# PTC_Heater_V2.net
KiCad netlist of a schematic drawn in Altium Designer
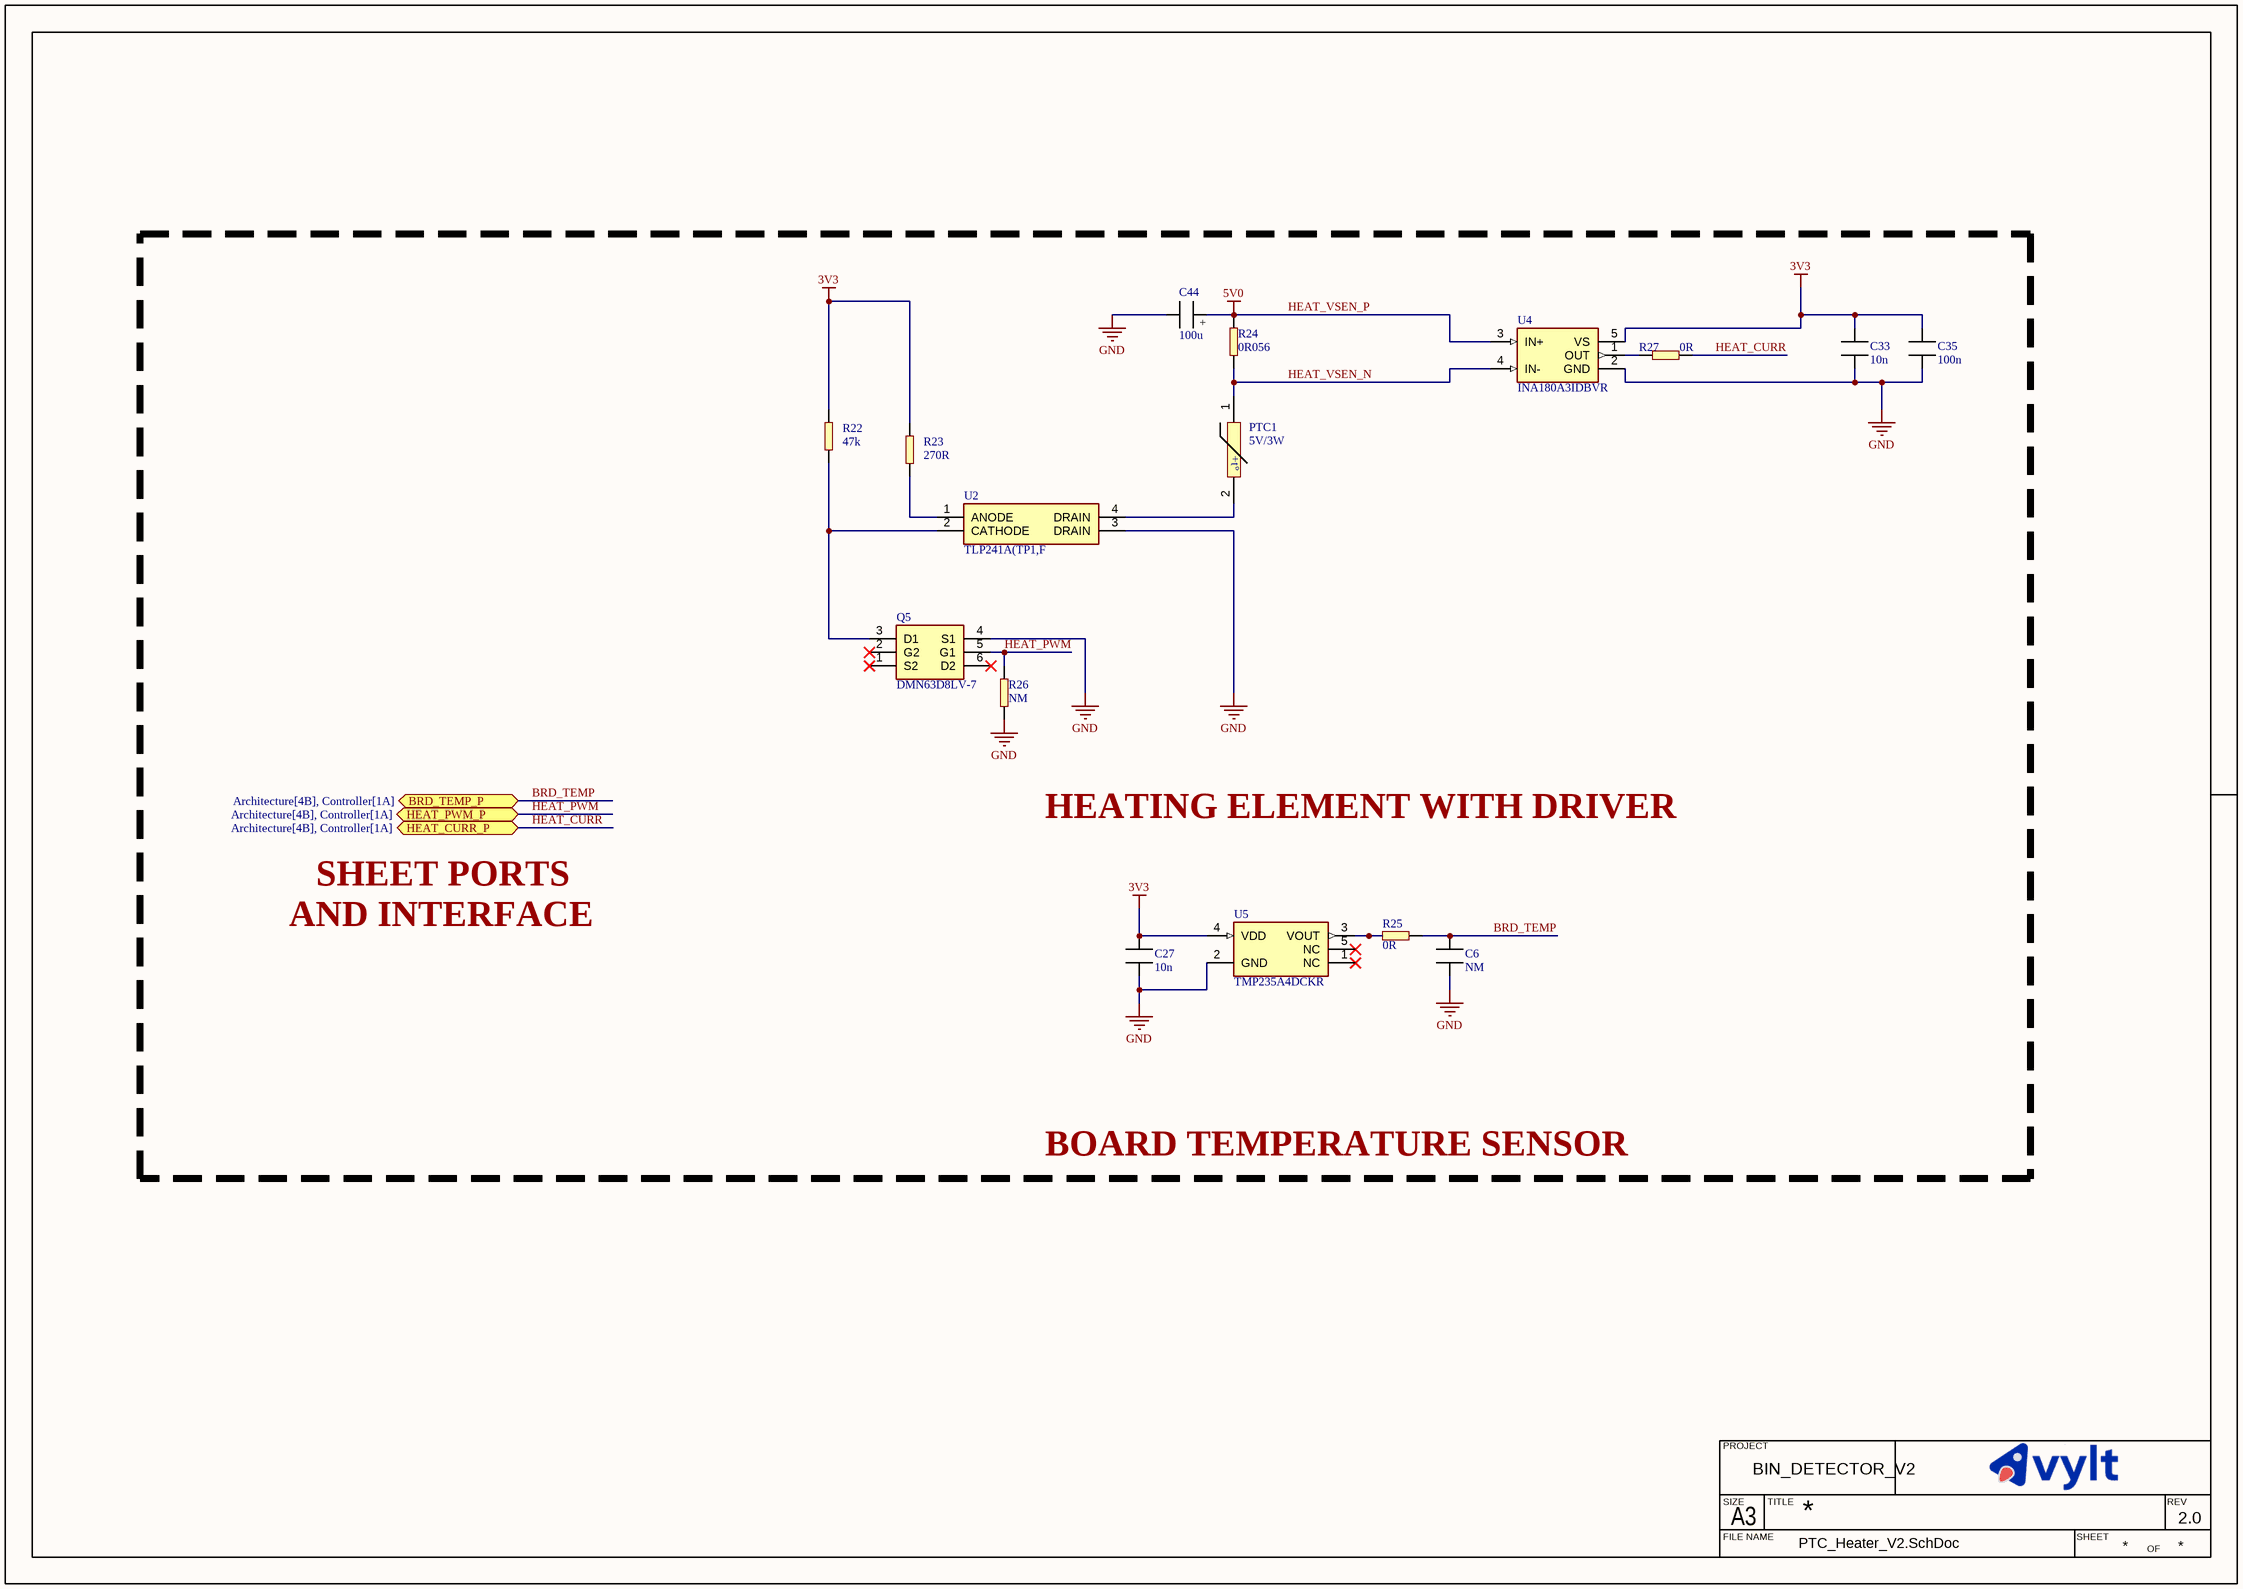
[diagram p0: PTC_Heater_V2.SchDoc]

(export (version "E")
  (design (tool "Eeschema 10.0.6"))
  (components
    (comp (ref "C6")
      (value "NM")
      (footprint "CAPC1608X10N")
      (description "Chip Capacitor, 2-Leads, Body 1.60x0.80mm, IPC Medium Density")
      (fields (field (name "Comment") "ERP_102-1"))
      (libsource (lib "Capacitor") (part "MLCC_0603"))
    )
    (comp (ref "C27")
      (value "10n")
      (footprint "CAPC1608X10N")
      (description "MLCC_0603")
      (fields (field (name "Comment") "ERP_102-1"))
      (libsource (lib "Capacitor") (part "MLCC_0603"))
    )
    (comp (ref "C33")
      (value "10n")
      (footprint "CAPC1608X10N")
      (description "Chip Capacitor, 2-Leads, Body 1.60x0.80mm, IPC Medium Density")
      (fields (field (name "Comment") "ERP_102-1"))
      (libsource (lib "Capacitor") (part "MLCC_0603"))
    )
    (comp (ref "C35")
      (value "100n")
      (footprint "CAPC1608X10N")
      (description "Chip Capacitor, 2-Leads, Body 1.60x0.80mm, IPC Medium Density")
      (fields (field (name "Comment") "ERP_102-1"))
      (libsource (lib "Capacitor") (part "MLCC_0603"))
    )
    (comp (ref "C44")
      (value "100u")
      (footprint "CAP_6.3_7.7")
      (description "Electrolytic Capacitor SMD 6.3x7.7")
      (fields (field (name "Comment") "ERP_102-2"))
      (libsource (lib "ElectrolyticCapacitor") (part "CAP_6.3_7.7"))
    )
    (comp (ref "PTC1")
      (value "5V/3W")
      (footprint "FIT0844")
      (description "PTC HEATER 5V 3W")
      (fields (field (name "Comment") "FIT0844"))
      (libsource (lib "PTC_Heater") (part "FIT0844"))
    )
    (comp (ref "Q5")
      (value "DMN63D8LV-7")
      (footprint "DMN63D8LV")
      (description "MOSFET 2N-CH 30V 0.26A SOT563")
      (fields (field (name "Comment") "DMN63D8LV"))
      (libsource (lib "MOSFET") (part "DMN63D8LV"))
    )
    (comp (ref "R22")
      (value "47k")
      (footprint "RES_0603")
      (description "RES_0603")
      (fields (field (name "Comment") "ERP_101-1"))
      (libsource (lib "") (part "RES_0603_3"))
    )
    (comp (ref "R23")
      (value "270R")
      (footprint "RES_0603")
      (description "RES_0603")
      (fields (field (name "Comment") "ERP_101-1"))
      (libsource (lib "") (part "RES_0603_3"))
    )
    (comp (ref "R24")
      (value "0R056")
      (footprint "RESC3115X06N")
      (description "RES_0805")
      (fields (field (name "Comment") "ERP_101-1"))
      (libsource (lib "Resistor") (part "RES_1206"))
    )
    (comp (ref "R25")
      (value "0R")
      (footprint "RES_0603")
      (description "RES_0603")
      (fields (field (name "Comment") "ERP_101-1"))
      (libsource (lib "") (part "RES_0603_2"))
    )
    (comp (ref "R26")
      (value "NM")
      (footprint "RES_0603")
      (description "RES_0603")
      (fields (field (name "Comment") "ERP_101-1"))
      (libsource (lib "") (part "RES_0603_1"))
    )
    (comp (ref "R27")
      (value "0R")
      (footprint "RES_0603")
      (description "RES_0603")
      (fields (field (name "Comment") "ERP_101-1"))
      (libsource (lib "Resistor") (part "RES_0603"))
    )
    (comp (ref "U2")
      (value "TLP241A(TP1,F")
      (footprint "TLP241A")
      (description "SSR RELAY SPST-NO 2A 0-40V")
      (fields (field (name "Comment") "TLP241A"))
      (libsource (lib "SSR") (part "TLP241A"))
    )
    (comp (ref "U4")
      (value "INA180A3IDBVR")
      (footprint "INA180")
      (fields (field (name "Comment") "INA180"))
      (libsource (lib "CurrentSenseOpAmp") (part "INA180"))
    )
    (comp (ref "U5")
      (value "TMP235A4DCKR")
      (footprint "TMP235")
      (fields (field (name "Comment") "TMP235"))
      (libsource (lib "AnalogTemp") (part "TMP235"))
    )
  )
  (nets
    (net (code "1") (name "/BRD_TEMP") (class "Default")
      (node (ref "C6") (pin "2") (pinfunction "2_2") (pintype "passive"))
      (node (ref "R25") (pin "2") (pinfunction "2_2") (pintype "passive"))
    )
    (net (code "2") (name "/HEAT_CURR") (class "Default")
      (node (ref "R27") (pin "1") (pinfunction "1_1") (pintype "passive"))
    )
    (net (code "3") (name "/HEAT_PWM") (class "Default")
      (node (ref "Q5") (pin "5") (pinfunction "G1_5") (pintype "passive"))
      (node (ref "R26") (pin "1") (pinfunction "1_1") (pintype "passive"))
    )
    (net (code "4") (name "/HEAT_VSEN_N") (class "Default")
      (node (ref "PTC1") (pin "1") (pinfunction "1_1") (pintype "passive"))
      (node (ref "R24") (pin "1") (pinfunction "1_1") (pintype "passive"))
      (node (ref "U4") (pin "4") (pinfunction "IN-_4") (pintype "input"))
    )
    (net (code "5") (name "3V3") (class "Default")
      (node (ref "C27") (pin "2") (pinfunction "2_2") (pintype "passive"))
      (node (ref "C33") (pin "2") (pinfunction "2_2") (pintype "passive"))
      (node (ref "C35") (pin "2") (pinfunction "2_2") (pintype "passive"))
      (node (ref "R22") (pin "2") (pinfunction "2_2") (pintype "passive"))
      (node (ref "R23") (pin "2") (pinfunction "2_2") (pintype "passive"))
      (node (ref "U4") (pin "5") (pinfunction "VS_5") (pintype "power_in"))
      (node (ref "U5") (pin "4") (pinfunction "VDD_4") (pintype "input"))
    )
    (net (code "6") (name "5V0") (class "Default")
      (node (ref "C44") (pin "1") (pinfunction "1_1") (pintype "passive"))
      (node (ref "R24") (pin "2") (pinfunction "2_2") (pintype "passive"))
      (node (ref "U4") (pin "3") (pinfunction "IN+_3") (pintype "input"))
    )
    (net (code "7") (name "GND") (class "Default")
      (node (ref "C27") (pin "1") (pinfunction "1_1") (pintype "passive"))
      (node (ref "C33") (pin "1") (pinfunction "1_1") (pintype "passive"))
      (node (ref "C35") (pin "1") (pinfunction "1_1") (pintype "passive"))
      (node (ref "C44") (pin "2") (pinfunction "2_2") (pintype "passive"))
      (node (ref "C6") (pin "1") (pinfunction "1_1") (pintype "passive"))
      (node (ref "Q5") (pin "4") (pinfunction "S1_4") (pintype "passive"))
      (node (ref "R26") (pin "2") (pinfunction "2_2") (pintype "passive"))
      (node (ref "U2") (pin "3") (pinfunction "DRAIN_3") (pintype "passive"))
      (node (ref "U4") (pin "2") (pinfunction "GND_2") (pintype "power_in"))
      (node (ref "U5") (pin "2") (pinfunction "GND_2") (pintype "power_in"))
    )
    (net (code "8") (name "Net-(PTC1-Pad2)") (class "Default")
      (node (ref "PTC1") (pin "2") (pinfunction "2_2") (pintype "passive"))
      (node (ref "U2") (pin "4") (pinfunction "DRAIN_4") (pintype "passive"))
    )
    (net (code "9") (name "Net-(Q5-D1)") (class "Default")
      (node (ref "Q5") (pin "3") (pinfunction "D1_3") (pintype "passive"))
      (node (ref "R22") (pin "1") (pinfunction "1_1") (pintype "passive"))
      (node (ref "U2") (pin "2") (pinfunction "CATHODE_2") (pintype "passive"))
    )
    (net (code "10") (name "Net-(U2-ANODE)") (class "Default")
      (node (ref "R23") (pin "1") (pinfunction "1_1") (pintype "passive"))
      (node (ref "U2") (pin "1") (pinfunction "ANODE_1") (pintype "passive"))
    )
    (net (code "11") (name "Net-(U4-OUT)") (class "Default")
      (node (ref "R27") (pin "2") (pinfunction "2_2") (pintype "passive"))
      (node (ref "U4") (pin "1") (pinfunction "OUT_1") (pintype "output"))
    )
    (net (code "12") (name "Net-(U5-VOUT)") (class "Default")
      (node (ref "R25") (pin "1") (pinfunction "1_1") (pintype "passive"))
      (node (ref "U5") (pin "3") (pinfunction "VOUT_3") (pintype "output"))
    )
    (net (code "13") (name "unconnected-(Q5-D2-Pad6)") (class "Default")
      (node (ref "Q5") (pin "6") (pinfunction "D2_6") (pintype "passive+no_connect"))
    )
    (net (code "14") (name "unconnected-(Q5-G2-Pad2)") (class "Default")
      (node (ref "Q5") (pin "2") (pinfunction "G2_2") (pintype "passive+no_connect"))
    )
    (net (code "15") (name "unconnected-(Q5-S2-Pad1)") (class "Default")
      (node (ref "Q5") (pin "1") (pinfunction "S2_1") (pintype "passive+no_connect"))
    )
    (net (code "16") (name "unconnected-(U5-NC-Pad1)") (class "Default")
      (node (ref "U5") (pin "1") (pinfunction "NC_1") (pintype "passive+no_connect"))
    )
    (net (code "17") (name "unconnected-(U5-NC-Pad5)") (class "Default")
      (node (ref "U5") (pin "5") (pinfunction "NC_5") (pintype "passive+no_connect"))
    )
  )
)
